# RCD300_AMPLIFIER_P1.net
KiCad netlist of a schematic drawn in Altium Designer
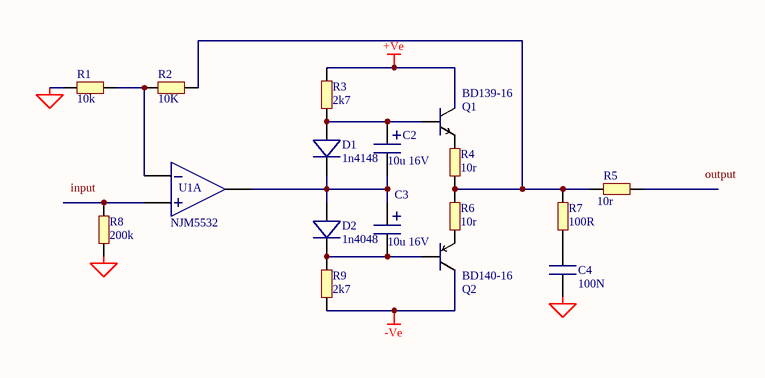
[diagram p0: RCD300_AMPLIFIER_P1.SchDoc]

(export (version "E")
  (design (tool "Eeschema 10.0.6"))
  (components
    (comp (ref "C2")
      (value "10u 16V")
      (footprint "CAP CASE B")
      (description "Standard Case B Electrolytic Capacitor")
      (fields (field (name "VOLTAGE") "16"))
      (libsource (lib "SMD Capacitors") (part "CAP CASE B"))
    )
    (comp (ref "C3")
      (value "10u 16V")
      (footprint "CAP CASE B")
      (description "Standard Case B Electrolytic Capacitor")
      (fields (field (name "VOLTAGE") "16"))
      (libsource (lib "SMD Capacitors") (part "CAP CASE B"))
    )
    (comp (ref "C4")
      (value "100N")
      (footprint "CAP 0805")
      (description "Standard 0805 Capacitor")
      (fields (field (name "VOLTAGE") "50V"))
      (libsource (lib "SMD Capacitors") (part "CAP 0805"))
    )
    (comp (ref "D1")
      (value "1n4148")
      (footprint "SOT-23")
      (description "SOT23 Diode")
      (libsource (lib "SMD Discretes") (part "DIODE SOT23"))
    )
    (comp (ref "D2")
      (value "1n4048")
      (footprint "SOT-23")
      (description "SOT23 Diode")
      (libsource (lib "SMD Discretes") (part "DIODE SOT23"))
    )
    (comp (ref "Q1")
      (value "BD139-16")
      (footprint "TO-126-V")
      (description "NPN TO126 Transistor")
      (libsource (lib "TH Discretes") (part "NPN TO-126"))
    )
    (comp (ref "Q2")
      (value "BD140-16")
      (footprint "TO-126-V")
      (description "PNP TO126 Transistor")
      (libsource (lib "TH Discretes") (part "PNP TO-126"))
    )
    (comp (ref "R1")
      (value "10k")
      (footprint "RES 0805")
      (description "Standard 0805 Resistor")
      (libsource (lib "") (part "RES 0805_1"))
    )
    (comp (ref "R2")
      (value "10K")
      (footprint "RES 0805")
      (description "Standard 0805 Resistor")
      (libsource (lib "") (part "RES 0805_1"))
    )
    (comp (ref "R3")
      (value "2k7")
      (footprint "RES 0805")
      (description "Standard 0805 Resistor")
      (libsource (lib "SMD Resistors") (part "RES 0805"))
    )
    (comp (ref "R4")
      (value "10r")
      (footprint "RES 1206")
      (description "Standard 1206 Resistor")
      (libsource (lib "SMD Resistors") (part "RES 1206"))
    )
    (comp (ref "R5")
      (value "10r")
      (footprint "RES 1206")
      (description "Standard 1206 Resistor")
      (libsource (lib "") (part "RES 1206_1"))
    )
    (comp (ref "R6")
      (value "10r")
      (footprint "RES 1206")
      (description "Standard 1206 Resistor")
      (libsource (lib "SMD Resistors") (part "RES 1206"))
    )
    (comp (ref "R7")
      (value "100R")
      (footprint "RES 0805")
      (description "Standard 0805 Resistor")
      (libsource (lib "SMD Resistors") (part "RES 0805"))
    )
    (comp (ref "R8")
      (value "200k")
      (footprint "RES 0805")
      (description "Standard 0805 Resistor")
      (libsource (lib "SMD Resistors") (part "RES 0805"))
    )
    (comp (ref "R9")
      (value "2k7")
      (footprint "RES 0805")
      (description "Standard 0805 Resistor")
      (libsource (lib "SMD Resistors") (part "RES 0805"))
    )
    (comp (ref "U1")
      (value "NJM5532")
      (footprint "DIP-8 SOCKETED")
      (description "Dual OPAMP DIP8 socketed")
      (libsource (lib "TH IC Analogue") (part "DUAL OPAMP DIP8 SKT"))
    )
  )
  (nets
    (net (code "1") (name "+Ve") (class "Default")
      (node (ref "Q1") (pin "2") (pinfunction "C_2") (pintype "passive"))
      (node (ref "R3") (pin "2") (pinfunction "2_2") (pintype "passive"))
    )
    (net (code "2") (name "-Ve") (class "Default")
      (node (ref "Q2") (pin "2") (pinfunction "C_2") (pintype "passive"))
      (node (ref "R9") (pin "1") (pinfunction "1_1") (pintype "passive"))
    )
    (net (code "5") (name "Net-(C4-Pad2)") (class "Default")
      (node (ref "C4") (pin "2") (pinfunction "2_2") (pintype "passive"))
      (node (ref "R7") (pin "1") (pinfunction "1_1") (pintype "passive"))
    )
    (net (code "6") (name "Net-(D1-A)") (class "Default")
      (node (ref "C2") (pin "1") (pinfunction "1_1") (pintype "passive"))
      (node (ref "D1") (pin "1") (pinfunction "A_1") (pintype "passive"))
      (node (ref "Q1") (pin "3") (pinfunction "B_3") (pintype "passive"))
      (node (ref "R3") (pin "1") (pinfunction "1_1") (pintype "passive"))
    )
    (net (code "7") (name "Net-(D1-C)") (class "Default")
      (node (ref "C2") (pin "2") (pinfunction "2_2") (pintype "passive"))
      (node (ref "C3") (pin "1") (pinfunction "1_1") (pintype "passive"))
      (node (ref "D1") (pin "3") (pinfunction "C_3") (pintype "passive"))
      (node (ref "D2") (pin "1") (pinfunction "A_1") (pintype "passive"))
      (node (ref "U1") (pin "1") (pinfunction "OUTPUT_1") (pintype "passive"))
    )
    (net (code "8") (name "Net-(D2-C)") (class "Default")
      (node (ref "C3") (pin "2") (pinfunction "2_2") (pintype "passive"))
      (node (ref "D2") (pin "3") (pinfunction "C_3") (pintype "passive"))
      (node (ref "Q2") (pin "3") (pinfunction "B_3") (pintype "passive"))
      (node (ref "R9") (pin "2") (pinfunction "2_2") (pintype "passive"))
    )
    (net (code "9") (name "Net-(Q1-E)") (class "Default")
      (node (ref "Q1") (pin "1") (pinfunction "E_1") (pintype "passive"))
      (node (ref "R4") (pin "1") (pinfunction "1_1") (pintype "passive"))
    )
    (net (code "10") (name "Net-(Q2-E)") (class "Default")
      (node (ref "Q2") (pin "1") (pinfunction "E_1") (pintype "passive"))
      (node (ref "R6") (pin "2") (pinfunction "2_2") (pintype "passive"))
    )
    (net (code "11") (name "Net-(R2-Pad2)") (class "Default")
      (node (ref "R2") (pin "2") (pinfunction "2_2") (pintype "passive"))
      (node (ref "R4") (pin "2") (pinfunction "2_2") (pintype "passive"))
      (node (ref "R5") (pin "1") (pinfunction "1_1") (pintype "passive"))
      (node (ref "R6") (pin "1") (pinfunction "1_1") (pintype "passive"))
      (node (ref "R7") (pin "2") (pinfunction "2_2") (pintype "passive"))
    )
    (net (code "12") (name "Net-(U1A-INV)") (class "Default")
      (node (ref "R1") (pin "2") (pinfunction "2_2") (pintype "passive"))
      (node (ref "R2") (pin "1") (pinfunction "1_1") (pintype "passive"))
      (node (ref "U1") (pin "2") (pinfunction "INV_2") (pintype "passive"))
    )
    (net (code "13") (name "Net-(U1A-NONINV)") (class "Default")
      (node (ref "R8") (pin "2") (pinfunction "2_2") (pintype "passive"))
      (node (ref "U1") (pin "3") (pinfunction "NONINV_3") (pintype "passive"))
    )
    (net (code "14") (name "SGND") (class "Default")
      (node (ref "C4") (pin "1") (pinfunction "1_1") (pintype "passive"))
      (node (ref "R1") (pin "1") (pinfunction "1_1") (pintype "passive"))
      (node (ref "R8") (pin "1") (pinfunction "1_1") (pintype "passive"))
    )
    (net (code "15") (name "unconnected-(R5-Pad2)") (class "Default")
      (node (ref "R5") (pin "2") (pinfunction "2_2") (pintype "passive"))
    )
  )
)
